# jlink_f72.net
KiCad netlist of a schematic drawn in Altium Designer
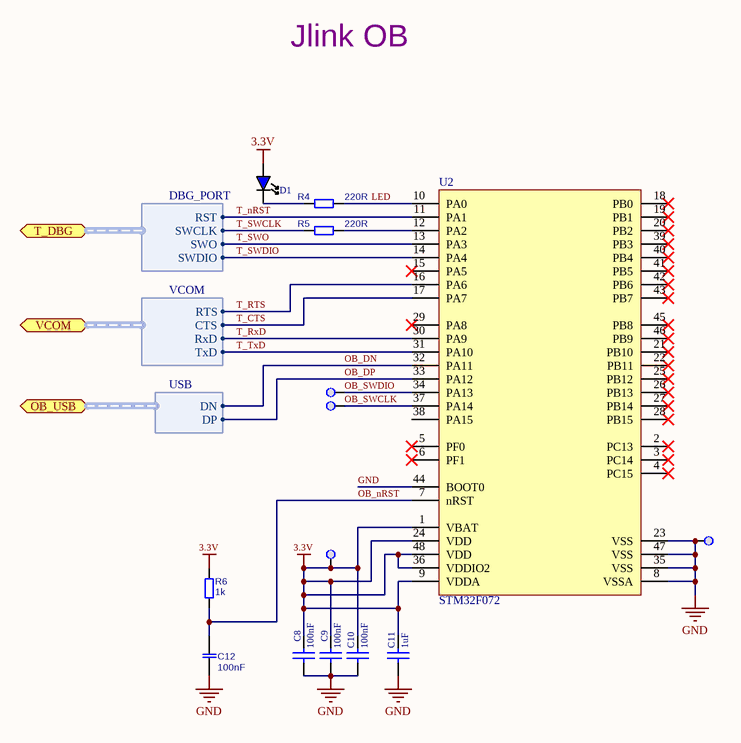
[diagram p0: jlink_f72.SchDoc]

(export (version "E")
  (design (tool "Eeschema 10.0.6"))
  (components
    (comp (ref "C8")
      (value "100nF")
      (footprint "C0402")
      (description "Capacitor")
      (fields (field (name "PUBLISHER") "Altium Limited"))
      (libsource (lib "Miscellaneous Devices") (part "Cap"))
    )
    (comp (ref "C9")
      (value "100nF")
      (footprint "C0402")
      (description "Capacitor")
      (fields (field (name "PUBLISHER") "Altium Limited"))
      (libsource (lib "Miscellaneous Devices") (part "Cap"))
    )
    (comp (ref "C10")
      (value "100nF")
      (footprint "C0402")
      (description "Capacitor")
      (fields (field (name "PUBLISHER") "Altium Limited"))
      (libsource (lib "Miscellaneous Devices") (part "Cap"))
    )
    (comp (ref "C11")
      (value "1uF")
      (footprint "C0603")
      (description "Capacitor")
      (fields (field (name "PUBLISHER") "Altium Limited"))
      (libsource (lib "Miscellaneous Devices") (part "Cap"))
    )
    (comp (ref "C12")
      (value "100nF")
      (footprint "C0402")
      (description "Ceramic Capacitor")
      (libsource (lib "hdesign") (part "Cap"))
    )
    (comp (ref "D1")
      (value "Debugger LED")
      (footprint "LED0603")
      (description "RED LED")
      (libsource (lib "hdesign") (part "LED_BLUE"))
    )
    (comp (ref "R4")
      (value "220R")
      (footprint "R0402")
      (description "Resistor")
      (libsource (lib "hdesign") (part "Res"))
    )
    (comp (ref "R5")
      (value "220R")
      (footprint "R0402")
      (description "Resistor")
      (libsource (lib "hdesign") (part "Res"))
    )
    (comp (ref "R6")
      (value "1k")
      (footprint "R0402")
      (description "Resistor")
      (libsource (lib "hdesign") (part "Res"))
    )
    (comp (ref "TP1")
      (value "TestPoint")
      (footprint "PAD1_07")
      (description "Test point")
      (libsource (lib "hdesign") (part "TestPoint"))
    )
    (comp (ref "TP2")
      (value "TestPoint")
      (footprint "PAD1_07")
      (description "Test point")
      (libsource (lib "hdesign") (part "TestPoint"))
    )
    (comp (ref "TP3")
      (value "TestPoint")
      (footprint "PAD1_07")
      (description "Test point")
      (libsource (lib "hdesign") (part "TestPoint"))
    )
    (comp (ref "TP4")
      (value "TestPoint")
      (footprint "PAD1_07")
      (description "Test point")
      (libsource (lib "hdesign") (part "TestPoint"))
    )
    (comp (ref "U2")
      (value "STM32F072")
      (footprint "LQFP48_M")
      (description "Cortex-M0 MCU")
      (libsource (lib "at32f415") (part "STM32F072"))
    )
  )
  (nets
    (net (code "4") (name "/LED") (class "Default")
      (node (ref "R4") (pin "1") (pinfunction "K_1") (pintype "passive"))
      (node (ref "U2") (pin "10") (pinfunction "PA0_10") (pintype "passive"))
    )
    (net (code "5") (name "/OB_DN") (class "Default")
      (node (ref "U2") (pin "32") (pinfunction "PA11_32") (pintype "passive"))
    )
    (net (code "6") (name "/OB_DP") (class "Default")
      (node (ref "U2") (pin "33") (pinfunction "PA12_33") (pintype "passive"))
    )
    (net (code "7") (name "/OB_SWCLK") (class "Default")
      (node (ref "TP2") (pin "1") (pinfunction "1_1") (pintype "passive"))
      (node (ref "U2") (pin "37") (pinfunction "PA14_37") (pintype "passive"))
    )
    (net (code "8") (name "/OB_SWDIO") (class "Default")
      (node (ref "TP1") (pin "1") (pinfunction "1_1") (pintype "passive"))
      (node (ref "U2") (pin "34") (pinfunction "PA13_34") (pintype "passive"))
    )
    (net (code "9") (name "/OB_nRST") (class "Default")
      (node (ref "C12") (pin "2") (pinfunction "A_2") (pintype "passive"))
      (node (ref "R6") (pin "2") (pinfunction "A_2") (pintype "passive"))
      (node (ref "U2") (pin "7") (pinfunction "nRST_7") (pintype "passive"))
    )
    (net (code "10") (name "/T_CTS") (class "Default")
      (node (ref "U2") (pin "17") (pinfunction "PA7_17") (pintype "passive"))
    )
    (net (code "11") (name "/T_RTS") (class "Default")
      (node (ref "U2") (pin "16") (pinfunction "PA6_16") (pintype "passive"))
    )
    (net (code "12") (name "/T_RxD") (class "Default")
      (node (ref "U2") (pin "30") (pinfunction "PA9_30") (pintype "passive"))
    )
    (net (code "13") (name "/T_SWCLK") (class "Default")
      (node (ref "R5") (pin "2") (pinfunction "A_2") (pintype "passive"))
    )
    (net (code "14") (name "/T_SWDIO") (class "Default")
      (node (ref "U2") (pin "14") (pinfunction "PA4_14") (pintype "passive"))
    )
    (net (code "15") (name "/T_SWO") (class "Default")
      (node (ref "U2") (pin "13") (pinfunction "PA3_13") (pintype "passive"))
    )
    (net (code "16") (name "/T_TxD") (class "Default")
      (node (ref "U2") (pin "31") (pinfunction "PA10_31") (pintype "passive"))
    )
    (net (code "17") (name "/T_nRST") (class "Default")
      (node (ref "U2") (pin "11") (pinfunction "PA1_11") (pintype "passive"))
    )
    (net (code "21") (name "3.3V") (class "Default")
      (node (ref "C10") (pin "1") (pinfunction "1_1") (pintype "passive"))
      (node (ref "C11") (pin "1") (pinfunction "1_1") (pintype "passive"))
      (node (ref "C8") (pin "1") (pinfunction "1_1") (pintype "passive"))
      (node (ref "C9") (pin "1") (pinfunction "1_1") (pintype "passive"))
      (node (ref "D1") (pin "A") (pinfunction "A_A") (pintype "passive"))
      (node (ref "R6") (pin "1") (pinfunction "K_1") (pintype "passive"))
      (node (ref "TP4") (pin "1") (pinfunction "1_1") (pintype "passive"))
      (node (ref "U2") (pin "1") (pinfunction "VBAT_1") (pintype "passive"))
      (node (ref "U2") (pin "24") (pinfunction "VDD_24") (pintype "passive"))
      (node (ref "U2") (pin "36") (pinfunction "VDDIO2_36") (pintype "passive"))
      (node (ref "U2") (pin "48") (pinfunction "VDD_48") (pintype "passive"))
      (node (ref "U2") (pin "9") (pinfunction "VDDA_9") (pintype "passive"))
    )
    (net (code "22") (name "GND") (class "Default")
      (node (ref "C10") (pin "2") (pinfunction "2_2") (pintype "passive"))
      (node (ref "C11") (pin "2") (pinfunction "2_2") (pintype "passive"))
      (node (ref "C12") (pin "1") (pinfunction "K_1") (pintype "passive"))
      (node (ref "C8") (pin "2") (pinfunction "2_2") (pintype "passive"))
      (node (ref "C9") (pin "2") (pinfunction "2_2") (pintype "passive"))
      (node (ref "TP3") (pin "1") (pinfunction "1_1") (pintype "passive"))
      (node (ref "U2") (pin "23") (pinfunction "VSS_23") (pintype "passive"))
      (node (ref "U2") (pin "35") (pinfunction "VSS_35") (pintype "passive"))
      (node (ref "U2") (pin "44") (pinfunction "BOOT0_44") (pintype "passive"))
      (node (ref "U2") (pin "47") (pinfunction "VSS_47") (pintype "passive"))
      (node (ref "U2") (pin "8") (pinfunction "VSSA_8") (pintype "passive"))
    )
    (net (code "23") (name "Net-(R4-A)") (class "Default")
      (node (ref "D1") (pin "k") (pinfunction "k_k") (pintype "passive"))
      (node (ref "R4") (pin "2") (pinfunction "A_2") (pintype "passive"))
    )
    (net (code "24") (name "Net-(R5-K)") (class "Default")
      (node (ref "R5") (pin "1") (pinfunction "K_1") (pintype "passive"))
      (node (ref "U2") (pin "12") (pinfunction "PA2_12") (pintype "passive"))
    )
    (net (code "25") (name "unconnected-(U2-PA5-Pad15)") (class "Default")
      (node (ref "U2") (pin "15") (pinfunction "PA5_15") (pintype "passive+no_connect"))
    )
    (net (code "26") (name "unconnected-(U2-PA8-Pad29)") (class "Default")
      (node (ref "U2") (pin "29") (pinfunction "PA8_29") (pintype "passive+no_connect"))
    )
    (net (code "27") (name "unconnected-(U2-PA15-Pad38)") (class "Default")
      (node (ref "U2") (pin "38") (pinfunction "PA15_38") (pintype "passive"))
    )
    (net (code "28") (name "unconnected-(U2-PB0-Pad18)") (class "Default")
      (node (ref "U2") (pin "18") (pinfunction "PB0_18") (pintype "passive+no_connect"))
    )
    (net (code "29") (name "unconnected-(U2-PB1-Pad19)") (class "Default")
      (node (ref "U2") (pin "19") (pinfunction "PB1_19") (pintype "passive+no_connect"))
    )
    (net (code "30") (name "unconnected-(U2-PB2-Pad20)") (class "Default")
      (node (ref "U2") (pin "20") (pinfunction "PB2_20") (pintype "passive+no_connect"))
    )
    (net (code "31") (name "unconnected-(U2-PB3-Pad39)") (class "Default")
      (node (ref "U2") (pin "39") (pinfunction "PB3_39") (pintype "passive+no_connect"))
    )
    (net (code "32") (name "unconnected-(U2-PB4-Pad40)") (class "Default")
      (node (ref "U2") (pin "40") (pinfunction "PB4_40") (pintype "passive+no_connect"))
    )
    (net (code "33") (name "unconnected-(U2-PB5-Pad41)") (class "Default")
      (node (ref "U2") (pin "41") (pinfunction "PB5_41") (pintype "passive+no_connect"))
    )
    (net (code "34") (name "unconnected-(U2-PB6-Pad42)") (class "Default")
      (node (ref "U2") (pin "42") (pinfunction "PB6_42") (pintype "passive+no_connect"))
    )
    (net (code "35") (name "unconnected-(U2-PB7-Pad43)") (class "Default")
      (node (ref "U2") (pin "43") (pinfunction "PB7_43") (pintype "passive+no_connect"))
    )
    (net (code "36") (name "unconnected-(U2-PB8-Pad45)") (class "Default")
      (node (ref "U2") (pin "45") (pinfunction "PB8_45") (pintype "passive+no_connect"))
    )
    (net (code "37") (name "unconnected-(U2-PB9-Pad46)") (class "Default")
      (node (ref "U2") (pin "46") (pinfunction "PB9_46") (pintype "passive+no_connect"))
    )
    (net (code "38") (name "unconnected-(U2-PB10-Pad21)") (class "Default")
      (node (ref "U2") (pin "21") (pinfunction "PB10_21") (pintype "passive+no_connect"))
    )
    (net (code "39") (name "unconnected-(U2-PB11-Pad22)") (class "Default")
      (node (ref "U2") (pin "22") (pinfunction "PB11_22") (pintype "passive+no_connect"))
    )
    (net (code "40") (name "unconnected-(U2-PB12-Pad25)") (class "Default")
      (node (ref "U2") (pin "25") (pinfunction "PB12_25") (pintype "passive+no_connect"))
    )
    (net (code "41") (name "unconnected-(U2-PB13-Pad26)") (class "Default")
      (node (ref "U2") (pin "26") (pinfunction "PB13_26") (pintype "passive+no_connect"))
    )
    (net (code "42") (name "unconnected-(U2-PB14-Pad27)") (class "Default")
      (node (ref "U2") (pin "27") (pinfunction "PB14_27") (pintype "passive+no_connect"))
    )
    (net (code "43") (name "unconnected-(U2-PB15-Pad28)") (class "Default")
      (node (ref "U2") (pin "28") (pinfunction "PB15_28") (pintype "passive+no_connect"))
    )
    (net (code "44") (name "unconnected-(U2-PC13-Pad2)") (class "Default")
      (node (ref "U2") (pin "2") (pinfunction "PC13_2") (pintype "passive+no_connect"))
    )
    (net (code "45") (name "unconnected-(U2-PC14-Pad3)") (class "Default")
      (node (ref "U2") (pin "3") (pinfunction "PC14_3") (pintype "passive+no_connect"))
    )
    (net (code "46") (name "unconnected-(U2-PC15-Pad4)") (class "Default")
      (node (ref "U2") (pin "4") (pinfunction "PC15_4") (pintype "passive+no_connect"))
    )
    (net (code "47") (name "unconnected-(U2-PF0-Pad5)") (class "Default")
      (node (ref "U2") (pin "5") (pinfunction "PF0_5") (pintype "passive+no_connect"))
    )
    (net (code "48") (name "unconnected-(U2-PF1-Pad6)") (class "Default")
      (node (ref "U2") (pin "6") (pinfunction "PF1_6") (pintype "passive+no_connect"))
    )
  )
)
